# DFF_1_0.net
KiCad netlist of a schematic drawn in EAGLE
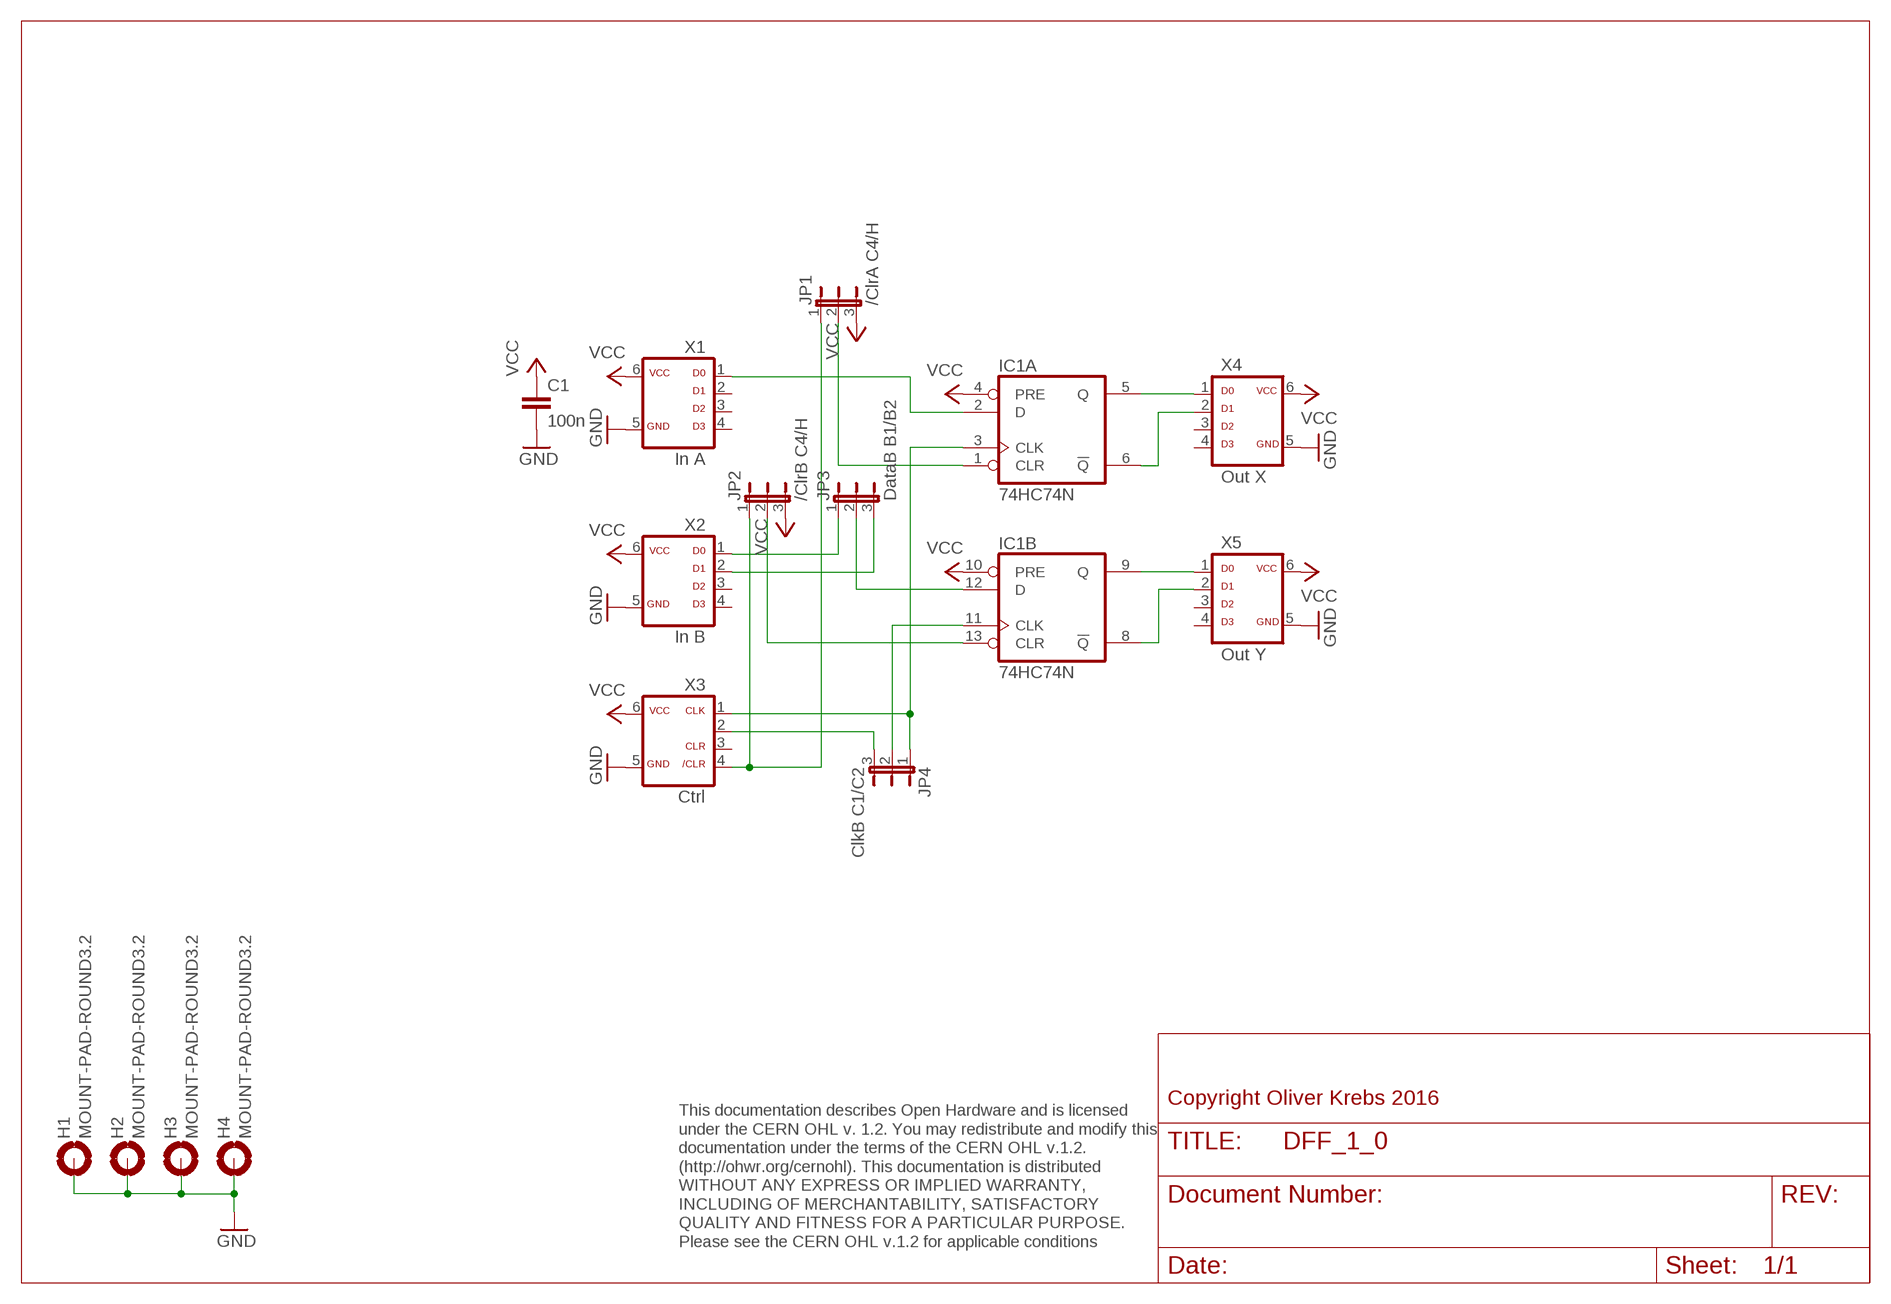
[diagram p0: schematic, sheet 1]

(export (version "E")
  (design (tool "Eeschema 10.0.6"))
  (components
    (comp (ref "C1")
      (value "100n")
      (footprint "eagle-import:C050-025X075")
      (libsource (lib "eagle-import") (part "C-EU050-025X075"))
    )
    (comp (ref "H1")
      (value "MOUNT-PAD-ROUND3.2")
      (footprint "eagle-import:3,2-PAD")
      (libsource (lib "eagle-import") (part "MOUNT-PAD-ROUND3.2"))
    )
    (comp (ref "H2")
      (value "MOUNT-PAD-ROUND3.2")
      (footprint "eagle-import:3,2-PAD")
      (libsource (lib "eagle-import") (part "MOUNT-PAD-ROUND3.2"))
    )
    (comp (ref "H3")
      (value "MOUNT-PAD-ROUND3.2")
      (footprint "eagle-import:3,2-PAD")
      (libsource (lib "eagle-import") (part "MOUNT-PAD-ROUND3.2"))
    )
    (comp (ref "H4")
      (value "MOUNT-PAD-ROUND3.2")
      (footprint "eagle-import:3,2-PAD")
      (libsource (lib "eagle-import") (part "MOUNT-PAD-ROUND3.2"))
    )
    (comp (ref "IC1")
      (value "74HC74N")
      (footprint "eagle-import:DIL14")
      (libsource (lib "eagle-import") (part "7474NHC"))
    )
    (comp (ref "JP1")
      (value "/ClrA C4/H")
      (footprint "eagle-import:JP2-U")
      (libsource (lib "eagle-import") (part "JP2EJP2-U"))
    )
    (comp (ref "JP2")
      (value "/ClrB C4/H")
      (footprint "eagle-import:JP2-U")
      (libsource (lib "eagle-import") (part "JP2EJP2-U"))
    )
    (comp (ref "JP3")
      (value "DataB B1/B2")
      (footprint "eagle-import:JP2-U")
      (libsource (lib "eagle-import") (part "JP2EJP2-U"))
    )
    (comp (ref "JP4")
      (value "ClkB C1/C2")
      (footprint "eagle-import:JP2-U")
      (libsource (lib "eagle-import") (part "JP2EJP2-U"))
    )
    (comp (ref "X1")
      (value "In A")
      (footprint "eagle-import:ML-6")
      (libsource (lib "eagle-import") (part "ML6D"))
    )
    (comp (ref "X2")
      (value "In B")
      (footprint "eagle-import:ML-6")
      (libsource (lib "eagle-import") (part "ML6D"))
    )
    (comp (ref "X3")
      (value "Ctrl")
      (footprint "eagle-import:ML-6")
      (libsource (lib "eagle-import") (part "ML6C"))
    )
    (comp (ref "X4")
      (value "Out X")
      (footprint "eagle-import:ML-6")
      (libsource (lib "eagle-import") (part "ML6D"))
    )
    (comp (ref "X5")
      (value "Out Y")
      (footprint "eagle-import:ML-6")
      (libsource (lib "eagle-import") (part "ML6D"))
    )
  )
  (nets
    (net (code "1") (name "GND") (class "Default")
      (node (ref "C1") (pin "2") (pinfunction "2_2") (pintype "passive"))
      (node (ref "H1") (pin "B3,2") (pinfunction "MOUNT_B3,2") (pintype "passive"))
      (node (ref "H2") (pin "B3,2") (pinfunction "MOUNT_B3,2") (pintype "passive"))
      (node (ref "H3") (pin "B3,2") (pinfunction "MOUNT_B3,2") (pintype "passive"))
      (node (ref "H4") (pin "B3,2") (pinfunction "MOUNT_B3,2") (pintype "passive"))
      (node (ref "X1") (pin "5") (pinfunction "5_5") (pintype "passive"))
      (node (ref "X2") (pin "5") (pinfunction "5_5") (pintype "passive"))
      (node (ref "X3") (pin "5") (pinfunction "5_5") (pintype "passive"))
      (node (ref "X4") (pin "5") (pinfunction "5_5") (pintype "passive"))
      (node (ref "X5") (pin "5") (pinfunction "5_5") (pintype "passive"))
    )
    (net (code "2") (name "Net-(IC1A-CLK)") (class "Default")
      (node (ref "IC1") (pin "3") (pinfunction "CLK_3") (pintype "input"))
      (node (ref "JP4") (pin "1") (pinfunction "1_1") (pintype "passive"))
      (node (ref "X3") (pin "1") (pinfunction "1_1") (pintype "passive"))
    )
    (net (code "3") (name "Net-(IC1A-CLR)") (class "Default")
      (node (ref "IC1") (pin "1") (pinfunction "CLR_1") (pintype "input"))
      (node (ref "JP1") (pin "2") (pinfunction "2_2") (pintype "passive"))
    )
    (net (code "4") (name "Net-(IC1A-D)") (class "Default")
      (node (ref "IC1") (pin "2") (pinfunction "D_2") (pintype "input"))
      (node (ref "X1") (pin "1") (pinfunction "1_1") (pintype "passive"))
    )
    (net (code "5") (name "Net-(IC1A-Q)") (class "Default")
      (node (ref "IC1") (pin "5") (pinfunction "Q_5") (pintype "output"))
      (node (ref "X4") (pin "1") (pinfunction "1_1") (pintype "passive"))
    )
    (net (code "6") (name "Net-(IC1A-~{Q})") (class "Default")
      (node (ref "IC1") (pin "6") (pinfunction "~{Q}_6") (pintype "output"))
      (node (ref "X4") (pin "2") (pinfunction "2_2") (pintype "passive"))
    )
    (net (code "7") (name "Net-(IC1B-CLK)") (class "Default")
      (node (ref "IC1") (pin "11") (pinfunction "CLK_11") (pintype "input"))
      (node (ref "JP4") (pin "2") (pinfunction "2_2") (pintype "passive"))
    )
    (net (code "8") (name "Net-(IC1B-CLR)") (class "Default")
      (node (ref "IC1") (pin "13") (pinfunction "CLR_13") (pintype "input"))
      (node (ref "JP2") (pin "2") (pinfunction "2_2") (pintype "passive"))
    )
    (net (code "9") (name "Net-(IC1B-D)") (class "Default")
      (node (ref "IC1") (pin "12") (pinfunction "D_12") (pintype "input"))
      (node (ref "JP3") (pin "2") (pinfunction "2_2") (pintype "passive"))
    )
    (net (code "10") (name "Net-(IC1B-Q)") (class "Default")
      (node (ref "IC1") (pin "9") (pinfunction "Q_9") (pintype "output"))
      (node (ref "X5") (pin "1") (pinfunction "1_1") (pintype "passive"))
    )
    (net (code "11") (name "Net-(IC1B-~{Q})") (class "Default")
      (node (ref "IC1") (pin "8") (pinfunction "~{Q}_8") (pintype "output"))
      (node (ref "X5") (pin "2") (pinfunction "2_2") (pintype "passive"))
    )
    (net (code "12") (name "Net-(JP1-Pad1)") (class "Default")
      (node (ref "JP1") (pin "1") (pinfunction "1_1") (pintype "passive"))
      (node (ref "JP2") (pin "1") (pinfunction "1_1") (pintype "passive"))
      (node (ref "X3") (pin "4") (pinfunction "4_4") (pintype "passive"))
    )
    (net (code "13") (name "Net-(JP3-Pad1)") (class "Default")
      (node (ref "JP3") (pin "1") (pinfunction "1_1") (pintype "passive"))
      (node (ref "X2") (pin "1") (pinfunction "1_1") (pintype "passive"))
    )
    (net (code "14") (name "Net-(JP3-Pad3)") (class "Default")
      (node (ref "JP3") (pin "3") (pinfunction "3_3") (pintype "passive"))
      (node (ref "X2") (pin "2") (pinfunction "2_2") (pintype "passive"))
    )
    (net (code "15") (name "Net-(JP4-Pad3)") (class "Default")
      (node (ref "JP4") (pin "3") (pinfunction "3_3") (pintype "passive"))
      (node (ref "X3") (pin "2") (pinfunction "2_2") (pintype "passive"))
    )
    (net (code "16") (name "VCC") (class "Default")
      (node (ref "C1") (pin "1") (pinfunction "1_1") (pintype "passive"))
      (node (ref "IC1") (pin "10") (pinfunction "PRE_10") (pintype "input"))
      (node (ref "IC1") (pin "4") (pinfunction "PRE_4") (pintype "input"))
      (node (ref "JP1") (pin "3") (pinfunction "3_3") (pintype "passive"))
      (node (ref "JP2") (pin "3") (pinfunction "3_3") (pintype "passive"))
      (node (ref "X1") (pin "6") (pinfunction "6_6") (pintype "passive"))
      (node (ref "X2") (pin "6") (pinfunction "6_6") (pintype "passive"))
      (node (ref "X3") (pin "6") (pinfunction "6_6") (pintype "passive"))
      (node (ref "X4") (pin "6") (pinfunction "6_6") (pintype "passive"))
      (node (ref "X5") (pin "6") (pinfunction "6_6") (pintype "passive"))
    )
    (net (code "17") (name "unconnected-(X1-Pad2)") (class "Default")
      (node (ref "X1") (pin "2") (pinfunction "2_2") (pintype "passive"))
    )
    (net (code "18") (name "unconnected-(X1-Pad3)") (class "Default")
      (node (ref "X1") (pin "3") (pinfunction "3_3") (pintype "passive"))
    )
    (net (code "19") (name "unconnected-(X1-Pad4)") (class "Default")
      (node (ref "X1") (pin "4") (pinfunction "4_4") (pintype "passive"))
    )
    (net (code "20") (name "unconnected-(X2-Pad3)") (class "Default")
      (node (ref "X2") (pin "3") (pinfunction "3_3") (pintype "passive"))
    )
    (net (code "21") (name "unconnected-(X2-Pad4)") (class "Default")
      (node (ref "X2") (pin "4") (pinfunction "4_4") (pintype "passive"))
    )
    (net (code "22") (name "unconnected-(X3-Pad3)") (class "Default")
      (node (ref "X3") (pin "3") (pinfunction "3_3") (pintype "passive"))
    )
    (net (code "23") (name "unconnected-(X4-Pad3)") (class "Default")
      (node (ref "X4") (pin "3") (pinfunction "3_3") (pintype "passive"))
    )
    (net (code "24") (name "unconnected-(X4-Pad4)") (class "Default")
      (node (ref "X4") (pin "4") (pinfunction "4_4") (pintype "passive"))
    )
    (net (code "25") (name "unconnected-(X5-Pad3)") (class "Default")
      (node (ref "X5") (pin "3") (pinfunction "3_3") (pintype "passive"))
    )
    (net (code "26") (name "unconnected-(X5-Pad4)") (class "Default")
      (node (ref "X5") (pin "4") (pinfunction "4_4") (pintype "passive"))
    )
  )
)
